# PowerSystem_-_v_1_0.net
KiCad netlist of a schematic drawn in EAGLE
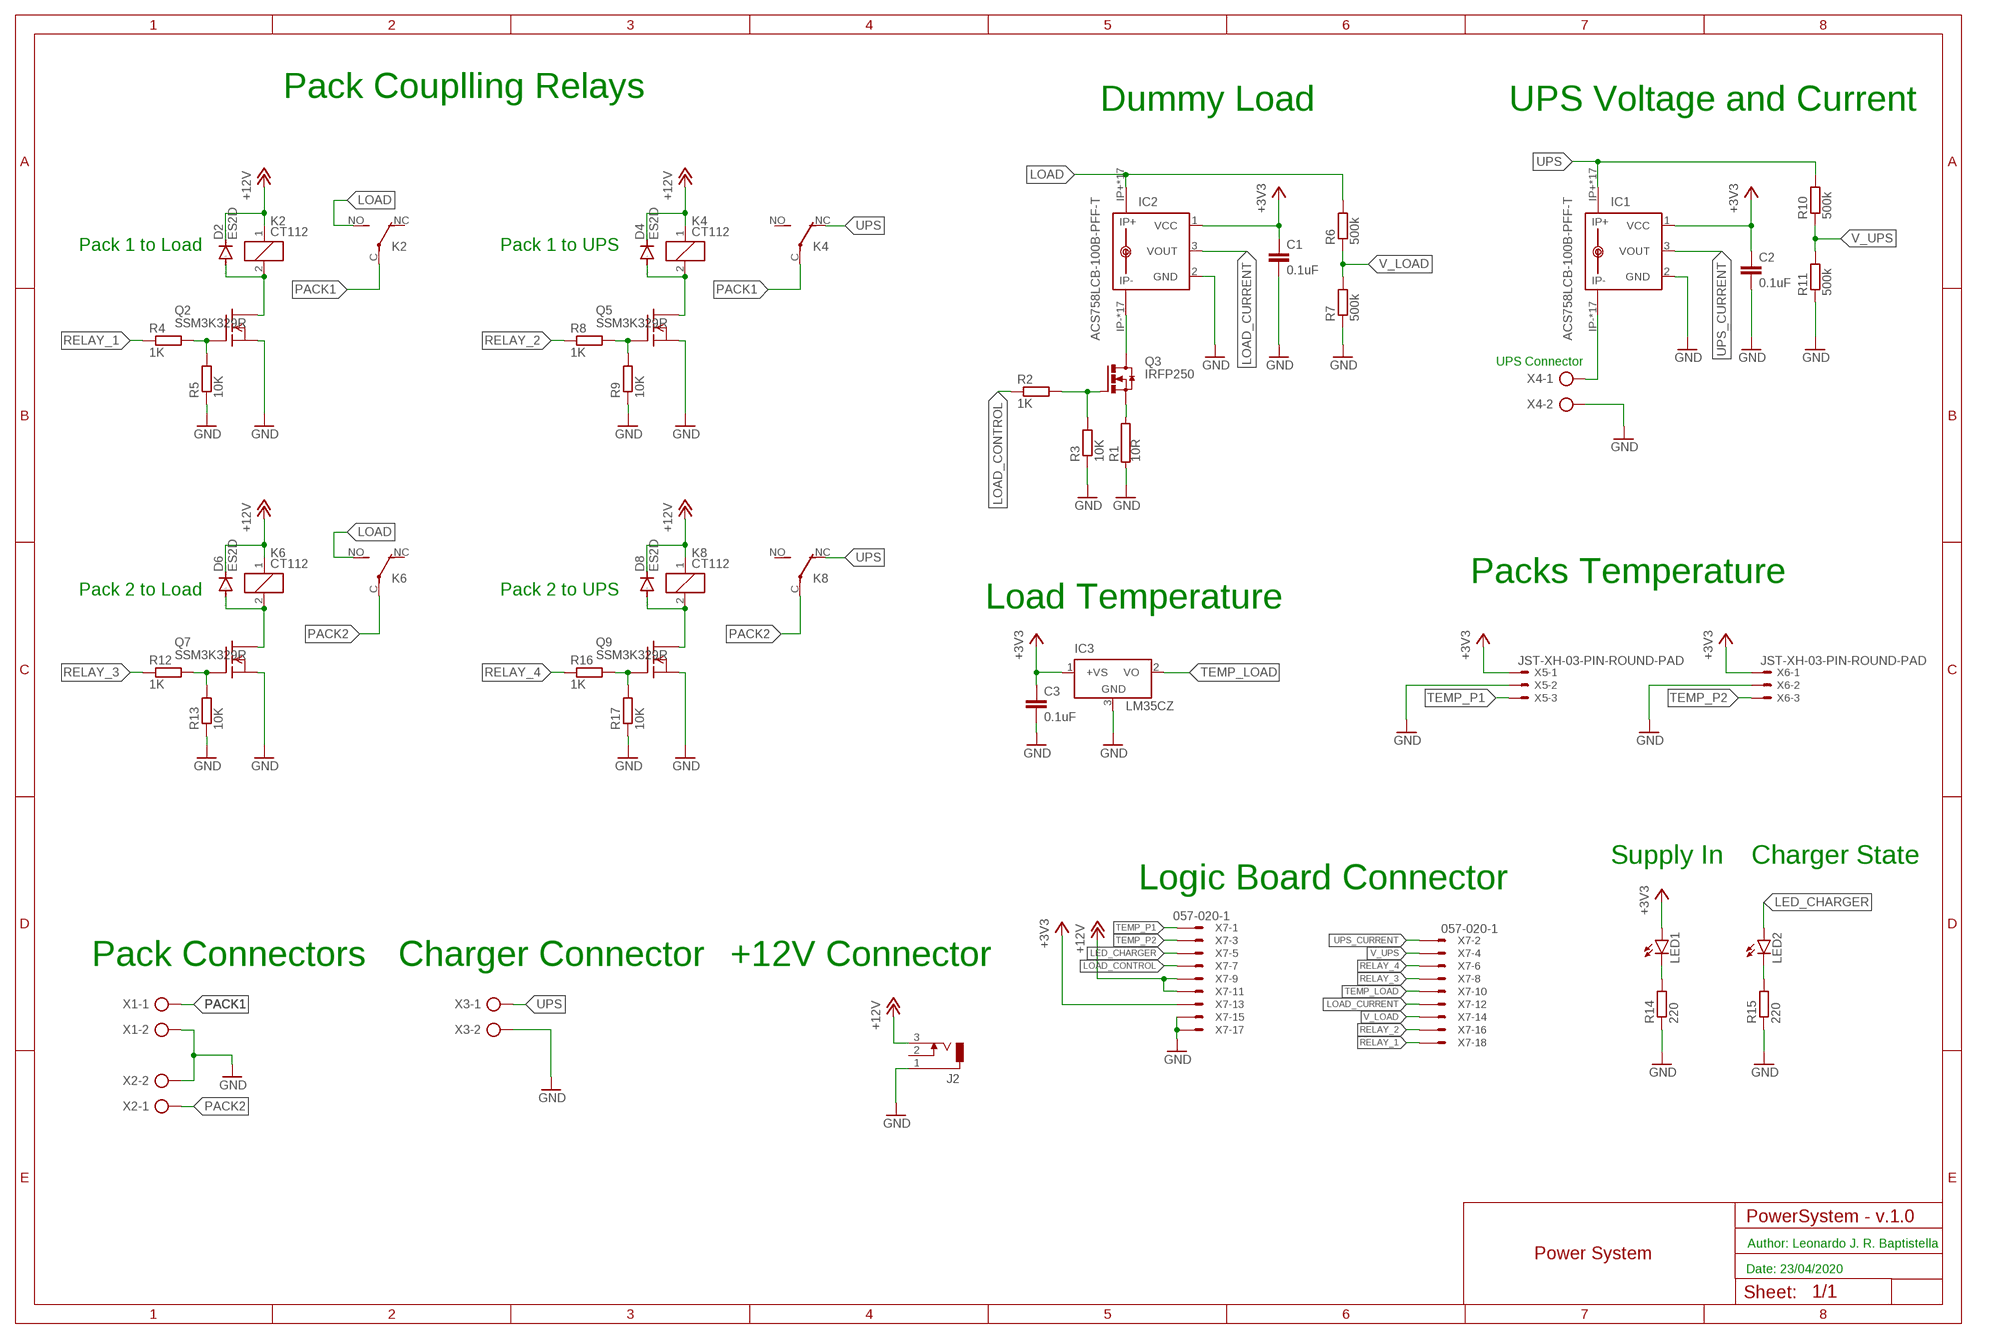
[diagram p0: schematic, sheet 1]

(export (version "E")
  (design (tool "Eeschema 10.0.6"))
  (components
    (comp (ref "C1")
      (value "0.1uF")
      (footprint "eagle-import:C1206")
      (libsource (lib "eagle-import") (part "C-EUC1206"))
    )
    (comp (ref "C2")
      (value "0.1uF")
      (footprint "eagle-import:C1206")
      (libsource (lib "eagle-import") (part "C-EUC1206"))
    )
    (comp (ref "C3")
      (value "0.1uF")
      (footprint "eagle-import:C1206")
      (libsource (lib "eagle-import") (part "C-EUC1206"))
    )
    (comp (ref "D2")
      (value "ES2D")
      (footprint "eagle-import:SMB")
      (libsource (lib "eagle-import") (part "ES2D"))
    )
    (comp (ref "D4")
      (value "ES2D")
      (footprint "eagle-import:SMB")
      (libsource (lib "eagle-import") (part "ES2D"))
    )
    (comp (ref "D6")
      (value "ES2D")
      (footprint "eagle-import:SMB")
      (libsource (lib "eagle-import") (part "ES2D"))
    )
    (comp (ref "D8")
      (value "ES2D")
      (footprint "eagle-import:SMB")
      (libsource (lib "eagle-import") (part "ES2D"))
    )
    (comp (ref "IC1")
      (value "ACS758LCB-100B-PFF-T")
      (footprint "eagle-import:CB-PFF")
      (libsource (lib "eagle-import") (part "ACS758LCB-100B-PFF-T"))
    )
    (comp (ref "IC2")
      (value "ACS758LCB-100B-PFF-T")
      (footprint "eagle-import:CB-PFF")
      (libsource (lib "eagle-import") (part "ACS758LCB-100B-PFF-T"))
    )
    (comp (ref "IC3")
      (value "LM35CZ")
      (footprint "eagle-import:TO92")
      (libsource (lib "eagle-import") (part "LM35CZ"))
    )
    (comp (ref "J2")
      (value "DCJ0303")
      (footprint "eagle-import:DCJ0303")
      (libsource (lib "eagle-import") (part "DCJ0303"))
    )
    (comp (ref "K2")
      (value "CT112")
      (footprint "eagle-import:CT-SLIM")
      (libsource (lib "eagle-import") (part "CT112"))
    )
    (comp (ref "K4")
      (value "CT112")
      (footprint "eagle-import:CT-SLIM")
      (libsource (lib "eagle-import") (part "CT112"))
    )
    (comp (ref "K6")
      (value "CT112")
      (footprint "eagle-import:CT-SLIM")
      (libsource (lib "eagle-import") (part "CT112"))
    )
    (comp (ref "K8")
      (value "CT112")
      (footprint "eagle-import:CT-SLIM")
      (libsource (lib "eagle-import") (part "CT112"))
    )
    (comp (ref "LED1")
      (value "LEDCHIPLED_1206")
      (footprint "eagle-import:CHIPLED_1206")
      (libsource (lib "eagle-import") (part "LEDCHIPLED_1206"))
    )
    (comp (ref "LED2")
      (value "LEDCHIPLED_1206")
      (footprint "eagle-import:CHIPLED_1206")
      (libsource (lib "eagle-import") (part "LEDCHIPLED_1206"))
    )
    (comp (ref "Q2")
      (value "SSM3K329R")
      (footprint "eagle-import:SOT23")
      (fields (field (name "MF") "STMicroelectronics") (field (name "MP") "2N7002"))
      (libsource (lib "eagle-import") (part "SSM3K329R"))
    )
    (comp (ref "Q3")
      (value "IRFP250")
      (footprint "eagle-import:TO-247AD-V")
      (libsource (lib "eagle-import") (part "IRFP250"))
    )
    (comp (ref "Q5")
      (value "SSM3K329R")
      (footprint "eagle-import:SOT23")
      (fields (field (name "MF") "STMicroelectronics") (field (name "MP") "2N7002"))
      (libsource (lib "eagle-import") (part "SSM3K329R"))
    )
    (comp (ref "Q7")
      (value "SSM3K329R")
      (footprint "eagle-import:SOT23")
      (fields (field (name "MF") "STMicroelectronics") (field (name "MP") "2N7002"))
      (libsource (lib "eagle-import") (part "SSM3K329R"))
    )
    (comp (ref "Q9")
      (value "SSM3K329R")
      (footprint "eagle-import:SOT23")
      (fields (field (name "MF") "STMicroelectronics") (field (name "MP") "2N7002"))
      (libsource (lib "eagle-import") (part "SSM3K329R"))
    )
    (comp (ref "R1")
      (value "10R")
      (footprint "eagle-import:HS25")
      (fields (field (name "MPN") "RHS25K"))
      (libsource (lib "eagle-import") (part "RHS25"))
    )
    (comp (ref "R2")
      (value "1K")
      (footprint "eagle-import:R1206")
      (libsource (lib "eagle-import") (part "R-EU_R1206"))
    )
    (comp (ref "R3")
      (value "10K")
      (footprint "eagle-import:R1206")
      (libsource (lib "eagle-import") (part "R-EU_R1206"))
    )
    (comp (ref "R4")
      (value "1K")
      (footprint "eagle-import:R1206")
      (libsource (lib "eagle-import") (part "R-EU_R1206"))
    )
    (comp (ref "R5")
      (value "10K")
      (footprint "eagle-import:R1206")
      (libsource (lib "eagle-import") (part "R-EU_R1206"))
    )
    (comp (ref "R6")
      (value "500k")
      (footprint "eagle-import:R1206")
      (libsource (lib "eagle-import") (part "R-EU_R1206"))
    )
    (comp (ref "R7")
      (value "500k")
      (footprint "eagle-import:R1206")
      (libsource (lib "eagle-import") (part "R-EU_R1206"))
    )
    (comp (ref "R8")
      (value "1K")
      (footprint "eagle-import:R1206")
      (libsource (lib "eagle-import") (part "R-EU_R1206"))
    )
    (comp (ref "R9")
      (value "10K")
      (footprint "eagle-import:R1206")
      (libsource (lib "eagle-import") (part "R-EU_R1206"))
    )
    (comp (ref "R10")
      (value "500k")
      (footprint "eagle-import:R1206")
      (libsource (lib "eagle-import") (part "R-EU_R1206"))
    )
    (comp (ref "R11")
      (value "500k")
      (footprint "eagle-import:R1206")
      (libsource (lib "eagle-import") (part "R-EU_R1206"))
    )
    (comp (ref "R12")
      (value "1K")
      (footprint "eagle-import:R1206")
      (libsource (lib "eagle-import") (part "R-EU_R1206"))
    )
    (comp (ref "R13")
      (value "10K")
      (footprint "eagle-import:R1206")
      (libsource (lib "eagle-import") (part "R-EU_R1206"))
    )
    (comp (ref "R14")
      (value "220")
      (footprint "eagle-import:R1206")
      (libsource (lib "eagle-import") (part "R-EU_R1206"))
    )
    (comp (ref "R15")
      (value "220")
      (footprint "eagle-import:R1206")
      (libsource (lib "eagle-import") (part "R-EU_R1206"))
    )
    (comp (ref "R16")
      (value "1K")
      (footprint "eagle-import:R1206")
      (libsource (lib "eagle-import") (part "R-EU_R1206"))
    )
    (comp (ref "R17")
      (value "10K")
      (footprint "eagle-import:R1206")
      (libsource (lib "eagle-import") (part "R-EU_R1206"))
    )
    (comp (ref "X1")
      (value "AK500/2-H")
      (footprint "eagle-import:AK500_2-H")
      (libsource (lib "eagle-import") (part "AK500/2-H"))
    )
    (comp (ref "X2")
      (value "AK500/2-H")
      (footprint "eagle-import:AK500_2-H")
      (libsource (lib "eagle-import") (part "AK500/2-H"))
    )
    (comp (ref "X3")
      (value "AK500/2-H")
      (footprint "eagle-import:AK500_2-H")
      (libsource (lib "eagle-import") (part "AK500/2-H"))
    )
    (comp (ref "X4")
      (value "AK500/2-H")
      (footprint "eagle-import:AK500_2-H")
      (libsource (lib "eagle-import") (part "AK500/2-H"))
    )
    (comp (ref "X5")
      (value "JST-XH-03-PIN-ROUND-PAD")
      (footprint "eagle-import:JST-XH-03-PACKAGE-ROUND-PAD")
      (libsource (lib "eagle-import") (part "JST-XH-03-PIN-ROUND-PAD"))
    )
    (comp (ref "X6")
      (value "JST-XH-03-PIN-ROUND-PAD")
      (footprint "eagle-import:JST-XH-03-PACKAGE-ROUND-PAD")
      (libsource (lib "eagle-import") (part "JST-XH-03-PIN-ROUND-PAD"))
    )
    (comp (ref "X7")
      (value "057-020-1")
      (footprint "eagle-import:057-020-1")
      (libsource (lib "eagle-import") (part "057-020-1"))
    )
  )
  (nets
    (net (code "1") (name "+3V3") (class "Default")
      (node (ref "C1") (pin "1") (pinfunction "1_1") (pintype "passive"))
      (node (ref "C2") (pin "1") (pinfunction "1_1") (pintype "passive"))
      (node (ref "C3") (pin "1") (pinfunction "1_1") (pintype "passive"))
      (node (ref "IC1") (pin "1") (pinfunction "VCC_1") (pintype "power_in"))
      (node (ref "IC2") (pin "1") (pinfunction "VCC_1") (pintype "power_in"))
      (node (ref "IC3") (pin "1") (pinfunction "+VS_1") (pintype "input"))
      (node (ref "LED1") (pin "A") (pinfunction "A_A") (pintype "passive"))
      (node (ref "X5") (pin "1") (pinfunction "S_1") (pintype "passive"))
      (node (ref "X6") (pin "1") (pinfunction "S_1") (pintype "passive"))
      (node (ref "X7") (pin "13") (pinfunction "S_13") (pintype "passive"))
    )
    (net (code "2") (name "+12V") (class "Default")
      (node (ref "D2") (pin "C") (pinfunction "C_C") (pintype "passive"))
      (node (ref "D4") (pin "C") (pinfunction "C_C") (pintype "passive"))
      (node (ref "D6") (pin "C") (pinfunction "C_C") (pintype "passive"))
      (node (ref "D8") (pin "C") (pinfunction "C_C") (pintype "passive"))
      (node (ref "J2") (pin "3") (pinfunction "3_3") (pintype "passive"))
      (node (ref "K2") (pin "1") (pinfunction "1_1") (pintype "passive"))
      (node (ref "K4") (pin "1") (pinfunction "1_1") (pintype "passive"))
      (node (ref "K6") (pin "1") (pinfunction "1_1") (pintype "passive"))
      (node (ref "K8") (pin "1") (pinfunction "1_1") (pintype "passive"))
      (node (ref "X7") (pin "11") (pinfunction "S_11") (pintype "passive"))
      (node (ref "X7") (pin "9") (pinfunction "S_9") (pintype "passive"))
    )
    (net (code "3") (name "GND") (class "Default")
      (node (ref "C1") (pin "2") (pinfunction "2_2") (pintype "passive"))
      (node (ref "C2") (pin "2") (pinfunction "2_2") (pintype "passive"))
      (node (ref "C3") (pin "2") (pinfunction "2_2") (pintype "passive"))
      (node (ref "IC1") (pin "2") (pinfunction "GND_2") (pintype "power_in"))
      (node (ref "IC2") (pin "2") (pinfunction "GND_2") (pintype "power_in"))
      (node (ref "IC3") (pin "3") (pinfunction "GND_3") (pintype "power_in"))
      (node (ref "J2") (pin "1") (pinfunction "1_1") (pintype "passive"))
      (node (ref "Q2") (pin "2") (pinfunction "S_2") (pintype "passive"))
      (node (ref "Q5") (pin "2") (pinfunction "S_2") (pintype "passive"))
      (node (ref "Q7") (pin "2") (pinfunction "S_2") (pintype "passive"))
      (node (ref "Q9") (pin "2") (pinfunction "S_2") (pintype "passive"))
      (node (ref "R1") (pin "1") (pinfunction "1_1") (pintype "passive"))
      (node (ref "R11") (pin "1") (pinfunction "1_1") (pintype "passive"))
      (node (ref "R13") (pin "1") (pinfunction "1_1") (pintype "passive"))
      (node (ref "R14") (pin "1") (pinfunction "1_1") (pintype "passive"))
      (node (ref "R15") (pin "1") (pinfunction "1_1") (pintype "passive"))
      (node (ref "R17") (pin "1") (pinfunction "1_1") (pintype "passive"))
      (node (ref "R3") (pin "1") (pinfunction "1_1") (pintype "passive"))
      (node (ref "R5") (pin "1") (pinfunction "1_1") (pintype "passive"))
      (node (ref "R7") (pin "1") (pinfunction "1_1") (pintype "passive"))
      (node (ref "R9") (pin "1") (pinfunction "1_1") (pintype "passive"))
      (node (ref "X1") (pin "2") (pinfunction "KL_2") (pintype "passive"))
      (node (ref "X2") (pin "2") (pinfunction "KL_2") (pintype "passive"))
      (node (ref "X3") (pin "2") (pinfunction "KL_2") (pintype "passive"))
      (node (ref "X4") (pin "2") (pinfunction "KL_2") (pintype "passive"))
      (node (ref "X5") (pin "2") (pinfunction "S_2") (pintype "passive"))
      (node (ref "X6") (pin "2") (pinfunction "S_2") (pintype "passive"))
      (node (ref "X7") (pin "15") (pinfunction "S_15") (pintype "passive"))
      (node (ref "X7") (pin "17") (pinfunction "S_17") (pintype "passive"))
    )
    (net (code "4") (name "LED_CHARGER") (class "Default")
      (node (ref "LED2") (pin "A") (pinfunction "A_A") (pintype "passive"))
      (node (ref "X7") (pin "5") (pinfunction "S_5") (pintype "passive"))
    )
    (net (code "5") (name "LOAD") (class "Default")
      (node (ref "IC2") (pin "IP+") (pinfunction "IP+_IP+") (pintype "passive"))
      (node (ref "IC2") (pin "IP+@10") (pinfunction "IP+_IP+@10") (pintype "passive"))
      (node (ref "IC2") (pin "IP+@11") (pinfunction "IP+_IP+@11") (pintype "passive"))
      (node (ref "IC2") (pin "IP+@12") (pinfunction "IP+_IP+@12") (pintype "passive"))
      (node (ref "IC2") (pin "IP+@13") (pinfunction "IP+_IP+@13") (pintype "passive"))
      (node (ref "IC2") (pin "IP+@14") (pinfunction "IP+_IP+@14") (pintype "passive"))
      (node (ref "IC2") (pin "IP+@15") (pinfunction "IP+_IP+@15") (pintype "passive"))
      (node (ref "IC2") (pin "IP+@16") (pinfunction "IP+_IP+@16") (pintype "passive"))
      (node (ref "IC2") (pin "IP+@17") (pinfunction "IP+_IP+@17") (pintype "passive"))
      (node (ref "IC2") (pin "IP+@2") (pinfunction "IP+_IP+@2") (pintype "passive"))
      (node (ref "IC2") (pin "IP+@3") (pinfunction "IP+_IP+@3") (pintype "passive"))
      (node (ref "IC2") (pin "IP+@4") (pinfunction "IP+_IP+@4") (pintype "passive"))
      (node (ref "IC2") (pin "IP+@5") (pinfunction "IP+_IP+@5") (pintype "passive"))
      (node (ref "IC2") (pin "IP+@6") (pinfunction "IP+_IP+@6") (pintype "passive"))
      (node (ref "IC2") (pin "IP+@7") (pinfunction "IP+_IP+@7") (pintype "passive"))
      (node (ref "IC2") (pin "IP+@8") (pinfunction "IP+_IP+@8") (pintype "passive"))
      (node (ref "IC2") (pin "IP+@9") (pinfunction "IP+_IP+@9") (pintype "passive"))
      (node (ref "K2") (pin "NO") (pinfunction "S_NO") (pintype "passive"))
      (node (ref "K6") (pin "NO") (pinfunction "S_NO") (pintype "passive"))
      (node (ref "R6") (pin "2") (pinfunction "2_2") (pintype "passive"))
    )
    (net (code "6") (name "LOAD_CONTROL") (class "Default")
      (node (ref "R2") (pin "1") (pinfunction "1_1") (pintype "passive"))
      (node (ref "X7") (pin "7") (pinfunction "S_7") (pintype "passive"))
    )
    (net (code "7") (name "LOAD_CURRENT") (class "Default")
      (node (ref "IC2") (pin "3") (pinfunction "VOUT_3") (pintype "output"))
      (node (ref "X7") (pin "12") (pinfunction "S_12") (pintype "passive"))
    )
    (net (code "8") (name "Net-(IC2-IP--PadIP-@10)") (class "Default")
      (node (ref "IC2") (pin "IP-") (pinfunction "IP-_IP-") (pintype "passive"))
      (node (ref "IC2") (pin "IP-@10") (pinfunction "IP-_IP-@10") (pintype "passive"))
      (node (ref "IC2") (pin "IP-@11") (pinfunction "IP-_IP-@11") (pintype "passive"))
      (node (ref "IC2") (pin "IP-@12") (pinfunction "IP-_IP-@12") (pintype "passive"))
      (node (ref "IC2") (pin "IP-@13") (pinfunction "IP-_IP-@13") (pintype "passive"))
      (node (ref "IC2") (pin "IP-@14") (pinfunction "IP-_IP-@14") (pintype "passive"))
      (node (ref "IC2") (pin "IP-@15") (pinfunction "IP-_IP-@15") (pintype "passive"))
      (node (ref "IC2") (pin "IP-@16") (pinfunction "IP-_IP-@16") (pintype "passive"))
      (node (ref "IC2") (pin "IP-@17") (pinfunction "IP-_IP-@17") (pintype "passive"))
      (node (ref "IC2") (pin "IP-@2") (pinfunction "IP-_IP-@2") (pintype "passive"))
      (node (ref "IC2") (pin "IP-@3") (pinfunction "IP-_IP-@3") (pintype "passive"))
      (node (ref "IC2") (pin "IP-@4") (pinfunction "IP-_IP-@4") (pintype "passive"))
      (node (ref "IC2") (pin "IP-@5") (pinfunction "IP-_IP-@5") (pintype "passive"))
      (node (ref "IC2") (pin "IP-@6") (pinfunction "IP-_IP-@6") (pintype "passive"))
      (node (ref "IC2") (pin "IP-@7") (pinfunction "IP-_IP-@7") (pintype "passive"))
      (node (ref "IC2") (pin "IP-@8") (pinfunction "IP-_IP-@8") (pintype "passive"))
      (node (ref "IC2") (pin "IP-@9") (pinfunction "IP-_IP-@9") (pintype "passive"))
      (node (ref "Q3") (pin "D") (pinfunction "D_D") (pintype "passive"))
    )
    (net (code "9") (name "Net-(LED1-PadC)") (class "Default")
      (node (ref "LED1") (pin "C") (pinfunction "C_C") (pintype "passive"))
      (node (ref "R14") (pin "2") (pinfunction "2_2") (pintype "passive"))
    )
    (net (code "10") (name "Net-(LED2-PadC)") (class "Default")
      (node (ref "LED2") (pin "C") (pinfunction "C_C") (pintype "passive"))
      (node (ref "R15") (pin "2") (pinfunction "2_2") (pintype "passive"))
    )
    (net (code "11") (name "Net-(Q2-D)") (class "Default")
      (node (ref "D2") (pin "A") (pinfunction "A_A") (pintype "passive"))
      (node (ref "K2") (pin "2") (pinfunction "2_2") (pintype "passive"))
      (node (ref "Q2") (pin "3") (pinfunction "D_3") (pintype "passive"))
    )
    (net (code "12") (name "Net-(Q2-G)") (class "Default")
      (node (ref "Q2") (pin "1") (pinfunction "G_1") (pintype "passive"))
      (node (ref "R4") (pin "2") (pinfunction "2_2") (pintype "passive"))
      (node (ref "R5") (pin "2") (pinfunction "2_2") (pintype "passive"))
    )
    (net (code "13") (name "Net-(Q3-PadG)") (class "Default")
      (node (ref "Q3") (pin "G") (pinfunction "G_G") (pintype "passive"))
      (node (ref "R2") (pin "2") (pinfunction "2_2") (pintype "passive"))
      (node (ref "R3") (pin "2") (pinfunction "2_2") (pintype "passive"))
    )
    (net (code "14") (name "Net-(Q3-PadS)") (class "Default")
      (node (ref "Q3") (pin "S") (pinfunction "S_S") (pintype "passive"))
      (node (ref "R1") (pin "2") (pinfunction "2_2") (pintype "passive"))
    )
    (net (code "15") (name "Net-(Q5-D)") (class "Default")
      (node (ref "D4") (pin "A") (pinfunction "A_A") (pintype "passive"))
      (node (ref "K4") (pin "2") (pinfunction "2_2") (pintype "passive"))
      (node (ref "Q5") (pin "3") (pinfunction "D_3") (pintype "passive"))
    )
    (net (code "16") (name "Net-(Q5-G)") (class "Default")
      (node (ref "Q5") (pin "1") (pinfunction "G_1") (pintype "passive"))
      (node (ref "R8") (pin "2") (pinfunction "2_2") (pintype "passive"))
      (node (ref "R9") (pin "2") (pinfunction "2_2") (pintype "passive"))
    )
    (net (code "17") (name "Net-(Q7-D)") (class "Default")
      (node (ref "D6") (pin "A") (pinfunction "A_A") (pintype "passive"))
      (node (ref "K6") (pin "2") (pinfunction "2_2") (pintype "passive"))
      (node (ref "Q7") (pin "3") (pinfunction "D_3") (pintype "passive"))
    )
    (net (code "18") (name "Net-(Q7-G)") (class "Default")
      (node (ref "Q7") (pin "1") (pinfunction "G_1") (pintype "passive"))
      (node (ref "R12") (pin "2") (pinfunction "2_2") (pintype "passive"))
      (node (ref "R13") (pin "2") (pinfunction "2_2") (pintype "passive"))
    )
    (net (code "19") (name "Net-(Q9-D)") (class "Default")
      (node (ref "D8") (pin "A") (pinfunction "A_A") (pintype "passive"))
      (node (ref "K8") (pin "2") (pinfunction "2_2") (pintype "passive"))
      (node (ref "Q9") (pin "3") (pinfunction "D_3") (pintype "passive"))
    )
    (net (code "20") (name "Net-(Q9-G)") (class "Default")
      (node (ref "Q9") (pin "1") (pinfunction "G_1") (pintype "passive"))
      (node (ref "R16") (pin "2") (pinfunction "2_2") (pintype "passive"))
      (node (ref "R17") (pin "2") (pinfunction "2_2") (pintype "passive"))
    )
    (net (code "21") (name "Net-(X4A-KL)") (class "Default")
      (node (ref "IC1") (pin "IP-") (pinfunction "IP-_IP-") (pintype "passive"))
      (node (ref "IC1") (pin "IP-@10") (pinfunction "IP-_IP-@10") (pintype "passive"))
      (node (ref "IC1") (pin "IP-@11") (pinfunction "IP-_IP-@11") (pintype "passive"))
      (node (ref "IC1") (pin "IP-@12") (pinfunction "IP-_IP-@12") (pintype "passive"))
      (node (ref "IC1") (pin "IP-@13") (pinfunction "IP-_IP-@13") (pintype "passive"))
      (node (ref "IC1") (pin "IP-@14") (pinfunction "IP-_IP-@14") (pintype "passive"))
      (node (ref "IC1") (pin "IP-@15") (pinfunction "IP-_IP-@15") (pintype "passive"))
      (node (ref "IC1") (pin "IP-@16") (pinfunction "IP-_IP-@16") (pintype "passive"))
      (node (ref "IC1") (pin "IP-@17") (pinfunction "IP-_IP-@17") (pintype "passive"))
      (node (ref "IC1") (pin "IP-@2") (pinfunction "IP-_IP-@2") (pintype "passive"))
      (node (ref "IC1") (pin "IP-@3") (pinfunction "IP-_IP-@3") (pintype "passive"))
      (node (ref "IC1") (pin "IP-@4") (pinfunction "IP-_IP-@4") (pintype "passive"))
      (node (ref "IC1") (pin "IP-@5") (pinfunction "IP-_IP-@5") (pintype "passive"))
      (node (ref "IC1") (pin "IP-@6") (pinfunction "IP-_IP-@6") (pintype "passive"))
      (node (ref "IC1") (pin "IP-@7") (pinfunction "IP-_IP-@7") (pintype "passive"))
      (node (ref "IC1") (pin "IP-@8") (pinfunction "IP-_IP-@8") (pintype "passive"))
      (node (ref "IC1") (pin "IP-@9") (pinfunction "IP-_IP-@9") (pintype "passive"))
      (node (ref "X4") (pin "1") (pinfunction "KL_1") (pintype "passive"))
    )
    (net (code "22") (name "PACK1") (class "Default")
      (node (ref "K2") (pin "C") (pinfunction "P_C") (pintype "passive"))
      (node (ref "K4") (pin "C") (pinfunction "P_C") (pintype "passive"))
      (node (ref "X1") (pin "1") (pinfunction "KL_1") (pintype "passive"))
    )
    (net (code "23") (name "PACK2") (class "Default")
      (node (ref "K6") (pin "C") (pinfunction "P_C") (pintype "passive"))
      (node (ref "K8") (pin "C") (pinfunction "P_C") (pintype "passive"))
      (node (ref "X2") (pin "1") (pinfunction "KL_1") (pintype "passive"))
    )
    (net (code "24") (name "RELAY_1") (class "Default")
      (node (ref "R4") (pin "1") (pinfunction "1_1") (pintype "passive"))
      (node (ref "X7") (pin "18") (pinfunction "S_18") (pintype "passive"))
    )
    (net (code "25") (name "RELAY_2") (class "Default")
      (node (ref "R8") (pin "1") (pinfunction "1_1") (pintype "passive"))
      (node (ref "X7") (pin "16") (pinfunction "S_16") (pintype "passive"))
    )
    (net (code "26") (name "RELAY_3") (class "Default")
      (node (ref "R12") (pin "1") (pinfunction "1_1") (pintype "passive"))
      (node (ref "X7") (pin "8") (pinfunction "S_8") (pintype "passive"))
    )
    (net (code "27") (name "RELAY_4") (class "Default")
      (node (ref "R16") (pin "1") (pinfunction "1_1") (pintype "passive"))
      (node (ref "X7") (pin "6") (pinfunction "S_6") (pintype "passive"))
    )
    (net (code "28") (name "TEMP_LOAD") (class "Default")
      (node (ref "IC3") (pin "2") (pinfunction "VO_2") (pintype "input"))
      (node (ref "X7") (pin "10") (pinfunction "S_10") (pintype "passive"))
    )
    (net (code "29") (name "TEMP_P1") (class "Default")
      (node (ref "X5") (pin "3") (pinfunction "S_3") (pintype "passive"))
      (node (ref "X7") (pin "1") (pinfunction "S_1") (pintype "passive"))
    )
    (net (code "30") (name "TEMP_P2") (class "Default")
      (node (ref "X6") (pin "3") (pinfunction "S_3") (pintype "passive"))
      (node (ref "X7") (pin "3") (pinfunction "S_3") (pintype "passive"))
    )
    (net (code "31") (name "UPS") (class "Default")
      (node (ref "IC1") (pin "IP+") (pinfunction "IP+_IP+") (pintype "passive"))
      (node (ref "IC1") (pin "IP+@10") (pinfunction "IP+_IP+@10") (pintype "passive"))
      (node (ref "IC1") (pin "IP+@11") (pinfunction "IP+_IP+@11") (pintype "passive"))
      (node (ref "IC1") (pin "IP+@12") (pinfunction "IP+_IP+@12") (pintype "passive"))
      (node (ref "IC1") (pin "IP+@13") (pinfunction "IP+_IP+@13") (pintype "passive"))
      (node (ref "IC1") (pin "IP+@14") (pinfunction "IP+_IP+@14") (pintype "passive"))
      (node (ref "IC1") (pin "IP+@15") (pinfunction "IP+_IP+@15") (pintype "passive"))
      (node (ref "IC1") (pin "IP+@16") (pinfunction "IP+_IP+@16") (pintype "passive"))
      (node (ref "IC1") (pin "IP+@17") (pinfunction "IP+_IP+@17") (pintype "passive"))
      (node (ref "IC1") (pin "IP+@2") (pinfunction "IP+_IP+@2") (pintype "passive"))
      (node (ref "IC1") (pin "IP+@3") (pinfunction "IP+_IP+@3") (pintype "passive"))
      (node (ref "IC1") (pin "IP+@4") (pinfunction "IP+_IP+@4") (pintype "passive"))
      (node (ref "IC1") (pin "IP+@5") (pinfunction "IP+_IP+@5") (pintype "passive"))
      (node (ref "IC1") (pin "IP+@6") (pinfunction "IP+_IP+@6") (pintype "passive"))
      (node (ref "IC1") (pin "IP+@7") (pinfunction "IP+_IP+@7") (pintype "passive"))
      (node (ref "IC1") (pin "IP+@8") (pinfunction "IP+_IP+@8") (pintype "passive"))
      (node (ref "IC1") (pin "IP+@9") (pinfunction "IP+_IP+@9") (pintype "passive"))
      (node (ref "K4") (pin "NC") (pinfunction "O_NC") (pintype "passive"))
      (node (ref "K8") (pin "NC") (pinfunction "O_NC") (pintype "passive"))
      (node (ref "R10") (pin "2") (pinfunction "2_2") (pintype "passive"))
      (node (ref "X3") (pin "1") (pinfunction "KL_1") (pintype "passive"))
    )
    (net (code "32") (name "UPS_CURRENT") (class "Default")
      (node (ref "IC1") (pin "3") (pinfunction "VOUT_3") (pintype "output"))
      (node (ref "X7") (pin "2") (pinfunction "S_2") (pintype "passive"))
    )
    (net (code "33") (name "V_LOAD") (class "Default")
      (node (ref "R6") (pin "1") (pinfunction "1_1") (pintype "passive"))
      (node (ref "R7") (pin "2") (pinfunction "2_2") (pintype "passive"))
      (node (ref "X7") (pin "14") (pinfunction "S_14") (pintype "passive"))
    )
    (net (code "34") (name "V_UPS") (class "Default")
      (node (ref "R10") (pin "1") (pinfunction "1_1") (pintype "passive"))
      (node (ref "R11") (pin "2") (pinfunction "2_2") (pintype "passive"))
      (node (ref "X7") (pin "4") (pinfunction "S_4") (pintype "passive"))
    )
    (net (code "35") (name "unconnected-(J2-Pad2)") (class "Default")
      (node (ref "J2") (pin "2") (pinfunction "2_2") (pintype "passive"))
    )
    (net (code "36") (name "unconnected-(K2B-O-PadNC)") (class "Default")
      (node (ref "K2") (pin "NC") (pinfunction "O_NC") (pintype "passive"))
    )
    (net (code "37") (name "unconnected-(K4B-S-PadNO)") (class "Default")
      (node (ref "K4") (pin "NO") (pinfunction "S_NO") (pintype "passive"))
    )
    (net (code "38") (name "unconnected-(K6B-O-PadNC)") (class "Default")
      (node (ref "K6") (pin "NC") (pinfunction "O_NC") (pintype "passive"))
    )
    (net (code "39") (name "unconnected-(K8B-S-PadNO)") (class "Default")
      (node (ref "K8") (pin "NO") (pinfunction "S_NO") (pintype "passive"))
    )
  )
)
